# emitter.net
KiCad netlist of a schematic drawn in Altium Designer
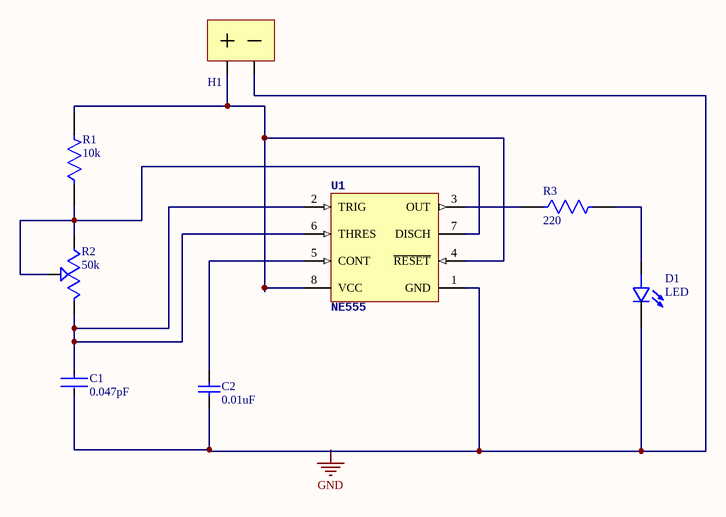
[diagram p0: emitter.SchDoc]

(export (version "E")
  (design (tool "Eeschema 10.0.6"))
  (components
    (comp (ref "C1")
      (value "0.047pF")
      (footprint "C0603C473M5RAC7867")
      (description "CAP CER 0.047UF 50V X7R 0603")
      (fields (field (name "TOLERANCE") "0.2") (field (name "MANUFACTURER") "KEMET"))
      (libsource (lib "course") (part "C0603C473M5RAC7867"))
    )
    (comp (ref "C2")
      (value "0.01uF")
      (footprint "CAPC1206(3216)100_L")
      (description "Cap Ceramic 0.01uF 50V X7R 10% SMD 1206 125°C Plastic T/R")
      (fields (field (name "TOLERANCE") "Â±10%"))
      (libsource (lib "course") (part "C1206C103K5RAC7025"))
    )
    (comp (ref "D1")
      (value "LED")
      (footprint "DIO_VSMY2853G")
      (description "850 nm 100 mA Â±28Â° Surface Mount High Speed Infrared Emitting Diode")
      (fields (field (name "MP") "VSMY2853G"))
      (libsource (lib "course") (part "VSMY2853G"))
    )
    (comp (ref "H1") (value "battery") (footprint "bat") (libsource (lib "course") (part "battery")))
    (comp (ref "R1")
      (value "10k")
      (footprint "FP-RMCF0805-IPC_A")
      (description "10kΩ ±5% 0.125W 0805 Thick Film Chip Resistor AEC-Q200 compliant")
      (fields (field (name "TOLERANCE") "5%"))
      (libsource (lib "course") (part "RMCF0805JT10K0"))
    )
    (comp (ref "R2")
      (value "50k")
      (footprint "TRIM_PVG5A503C03R00")
      (description "50 kOhms 0.25W, 1/4W J Lead Surface Mount Trimmer Potentiometer Cermet 11 Turn Top Adjustment")
      (fields (field (name "MF") "Bourns") (field (name "MP") "PVG5A503C03R00"))
      (libsource (lib "course") (part "PVG5A503C03R00"))
    )
    (comp (ref "R3")
      (value "220")
      (footprint "FP-MCU0805-IPC_A")
      (description "Res Thin Film 0805 220 Ohm 1% 1/8W 50ppm/C Molded SMD SMD Paper T/R")
      (fields (field (name "TOLERANCE") "1%"))
      (libsource (lib "course") (part "MCU08050C2200FP500"))
    )
    (comp (ref "U1")
      (value "NE555")
      (footprint "D0008A_L")
      (description "Precision Timer, 4.5 to 16 V, 0 to 70 degC, 8-Pin SOIC (D), Green (RoHS & no Sb/Br), Tube")
      (fields (field (name "MANUFACTURER") "Texas Instruments"))
      (libsource (lib "course") (part "NE555D"))
    )
  )
  (nets
    (net (code "2") (name "Net-(D1-Pad2)") (class "Default")
      (node (ref "D1") (pin "2") (pinfunction "2_2") (pintype "passive"))
      (node (ref "R3") (pin "2") (pinfunction "2_2") (pintype "passive"))
    )
    (net (code "3") (name "Net-(U1-CONT)") (class "Default")
      (node (ref "C2") (pin "2") (pinfunction "2_2") (pintype "passive"))
      (node (ref "U1") (pin "5") (pinfunction "CONT_5") (pintype "input"))
    )
    (net (code "4") (name "Net-(U1-DISCH)") (class "Default")
      (node (ref "R1") (pin "1") (pinfunction "1_1") (pintype "passive"))
      (node (ref "R2") (pin "1") (pinfunction "1_1") (pintype "passive"))
      (node (ref "R2") (pin "2") (pinfunction "2_2") (pintype "passive"))
      (node (ref "U1") (pin "7") (pinfunction "DISCH_7") (pintype "open_collector"))
    )
    (net (code "5") (name "Net-(U1-GND)") (class "Default")
      (node (ref "C1") (pin "2") (pinfunction "2_2") (pintype "passive"))
      (node (ref "C2") (pin "1") (pinfunction "1_1") (pintype "passive"))
      (node (ref "D1") (pin "1") (pinfunction "1_1") (pintype "passive"))
      (node (ref "H1") (pin "2") (pinfunction "2_2") (pintype "passive"))
      (node (ref "U1") (pin "1") (pinfunction "GND_1") (pintype "power_in"))
    )
    (net (code "6") (name "Net-(U1-OUT)") (class "Default")
      (node (ref "R3") (pin "1") (pinfunction "1_1") (pintype "passive"))
      (node (ref "U1") (pin "3") (pinfunction "OUT_3") (pintype "output"))
    )
    (net (code "7") (name "Net-(U1-THRES)") (class "Default")
      (node (ref "C1") (pin "1") (pinfunction "1_1") (pintype "passive"))
      (node (ref "R2") (pin "3") (pinfunction "3_3") (pintype "passive"))
      (node (ref "U1") (pin "2") (pinfunction "TRIG_2") (pintype "input"))
      (node (ref "U1") (pin "6") (pinfunction "THRES_6") (pintype "input"))
    )
    (net (code "8") (name "Net-(U1-VCC)") (class "Default")
      (node (ref "H1") (pin "1") (pinfunction "1_1") (pintype "passive"))
      (node (ref "R1") (pin "2") (pinfunction "2_2") (pintype "passive"))
      (node (ref "U1") (pin "4") (pinfunction "~{RESET}_4") (pintype "input"))
      (node (ref "U1") (pin "8") (pinfunction "VCC_8") (pintype "power_in"))
    )
  )
)
